# MCU.net
KiCad netlist of a schematic drawn in Altium Designer
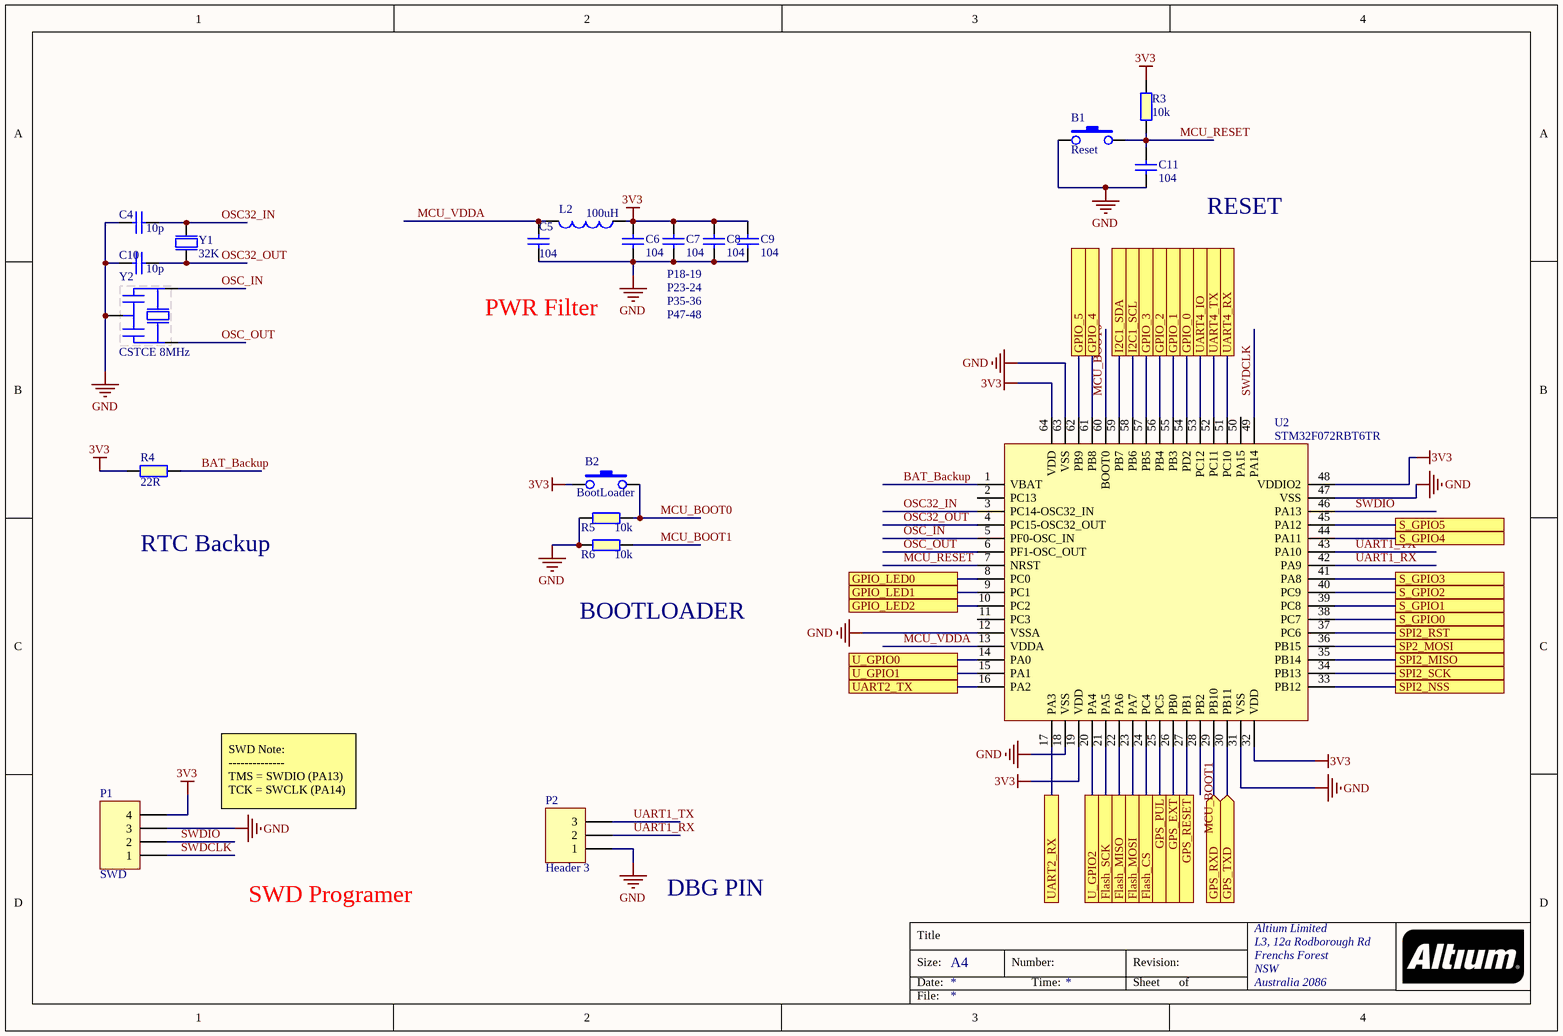
[diagram p0: MCU.SchDoc]

(export (version "E")
  (design (tool "Eeschema 10.0.6"))
  (components
    (comp (ref "B1")
      (value "Reset")
      (footprint "ThanhNT:TACTILE-SWITCH-1101NE")
      (libsource (lib "ThanhNT") (part "Button_2P_SMD"))
    )
    (comp (ref "B2")
      (value "BootLoader")
      (footprint "ThanhNT:TACTILE-SWITCH-1101NE")
      (libsource (lib "ThanhNT") (part "Button_2P_SMD"))
    )
    (comp (ref "C4")
      (value "10p")
      (footprint "C_0603")
      (description "Capacitor SMD")
      (fields (field (name "PUBLISHER") "Altium Limited"))
      (libsource (lib "ThanhNT") (part "Cap SMD 0805"))
    )
    (comp (ref "C5")
      (value "104")
      (footprint "C_0603")
      (description "Capacitor SMD")
      (fields (field (name "PUBLISHER") "Altium Limited"))
      (libsource (lib "ThanhNT") (part "Cap SMD 0805"))
    )
    (comp (ref "C6")
      (value "104")
      (footprint "C_0603")
      (description "Capacitor SMD")
      (fields (field (name "PUBLISHER") "Altium Limited"))
      (libsource (lib "ThanhNT") (part "Cap SMD 0805"))
    )
    (comp (ref "C7")
      (value "104")
      (footprint "C_0603")
      (description "Capacitor SMD")
      (fields (field (name "PUBLISHER") "Altium Limited"))
      (libsource (lib "ThanhNT") (part "Cap SMD 0805"))
    )
    (comp (ref "C8")
      (value "104")
      (footprint "C_0603")
      (description "Capacitor SMD")
      (fields (field (name "PUBLISHER") "Altium Limited"))
      (libsource (lib "ThanhNT") (part "Cap SMD 0805"))
    )
    (comp (ref "C9")
      (value "104")
      (footprint "C_0603")
      (description "Capacitor SMD")
      (fields (field (name "PUBLISHER") "Altium Limited"))
      (libsource (lib "ThanhNT") (part "Cap SMD 0805"))
    )
    (comp (ref "C10")
      (value "10p")
      (footprint "C_0603")
      (description "Capacitor SMD")
      (fields (field (name "PUBLISHER") "Altium Limited"))
      (libsource (lib "ThanhNT") (part "Cap SMD 0805"))
    )
    (comp (ref "C11")
      (value "104")
      (footprint "C_0603")
      (description "Capacitor SMD")
      (fields (field (name "PUBLISHER") "Altium Limited"))
      (libsource (lib "ThanhNT") (part "Cap SMD 0805"))
    )
    (comp (ref "L2")
      (value "100uH")
      (footprint "INDUCTOR_0603")
      (libsource (lib "ThanhNT") (part "INDUCTOR_0805"))
    )
    (comp (ref "P1")
      (value "SWD")
      (footprint "HDR1X4")
      (description "Header, 4-Pin")
      (fields (field (name "PUBLISHER") "Altium Limited"))
      (libsource (lib "Header") (part "Header 4"))
    )
    (comp (ref "P2")
      (value "Header 3")
      (footprint "HDR1X3")
      (description "Header, 3-Pin")
      (fields (field (name "PUBLISHER") "Altium Limited"))
      (libsource (lib "Header") (part "Header 3"))
    )
    (comp (ref "R3") (value "10k") (footprint "R_0603") (libsource (lib "ThanhNT") (part "RESISTOR_0805")))
    (comp (ref "R4") (value "22R") (footprint "R_0603") (libsource (lib "") (part "RESISTOR_0805_1")))
    (comp (ref "R5") (value "10k") (footprint "R_0603") (libsource (lib "") (part "RESISTOR_0805_1")))
    (comp (ref "R6") (value "10k") (footprint "R_0603") (libsource (lib "") (part "RESISTOR_0805_1")))
    (comp (ref "U2")
      (value "STM32F072RBT6TR")
      (footprint "STM32L072RBT")
      (description "IC MCU 32BIT 128KB FLASH 64LQFP")
      (fields
        (field (name "MANUFACTURER") "STMicroelectronics")
        (field (name "MANUFACTURER PART NUMBER") "STM32F072RBT6")
      )
      (libsource (lib "Node") (part "STM32F072RBT6TR"))
    )
    (comp (ref "Y1")
      (value "32K")
      (footprint "Crystal_2P")
      (fields (field (name "Comment") "Crystal_2P"))
      (libsource (lib "ThanhNT") (part "Crystal_2P"))
    )
    (comp (ref "Y2")
      (value "CSTCE 8MHz")
      (footprint "Crystal_4P")
      (description "(T) Crystal MHz with Capacitance Built-in")
      (libsource (lib "ThanhNT") (part "Crystal_CSTCE"))
    )
  )
  (nets
    (net (code "1") (name "/BAT_Backup") (class "Default")
      (node (ref "R4") (pin "2") (pinfunction "2_2") (pintype "passive"))
      (node (ref "U2") (pin "1") (pinfunction "VBAT_1") (pintype "passive"))
    )
    (net (code "2") (name "/Flash_CS") (class "Default")
      (node (ref "U2") (pin "24") (pinfunction "PC4_24") (pintype "passive"))
    )
    (net (code "3") (name "/Flash_MISO") (class "Default")
      (node (ref "U2") (pin "22") (pinfunction "PA6_22") (pintype "passive"))
    )
    (net (code "4") (name "/Flash_MOSI") (class "Default")
      (node (ref "U2") (pin "23") (pinfunction "PA7_23") (pintype "passive"))
    )
    (net (code "5") (name "/Flash_SCK") (class "Default")
      (node (ref "U2") (pin "21") (pinfunction "PA5_21") (pintype "passive"))
    )
    (net (code "6") (name "/GPIO_0") (class "Default")
      (node (ref "U2") (pin "54") (pinfunction "PD2_54") (pintype "passive"))
    )
    (net (code "7") (name "/GPIO_1") (class "Default")
      (node (ref "U2") (pin "55") (pinfunction "PB3_55") (pintype "passive"))
    )
    (net (code "8") (name "/GPIO_2") (class "Default")
      (node (ref "U2") (pin "56") (pinfunction "PB4_56") (pintype "passive"))
    )
    (net (code "9") (name "/GPIO_3") (class "Default")
      (node (ref "U2") (pin "57") (pinfunction "PB5_57") (pintype "passive"))
    )
    (net (code "10") (name "/GPIO_4") (class "Default")
      (node (ref "U2") (pin "61") (pinfunction "PB8_61") (pintype "passive"))
    )
    (net (code "11") (name "/GPIO_5") (class "Default")
      (node (ref "U2") (pin "62") (pinfunction "PB9_62") (pintype "passive"))
    )
    (net (code "12") (name "/GPIO_LED0") (class "Default")
      (node (ref "U2") (pin "8") (pinfunction "PC0_8") (pintype "passive"))
    )
    (net (code "13") (name "/GPIO_LED1") (class "Default")
      (node (ref "U2") (pin "9") (pinfunction "PC1_9") (pintype "passive"))
    )
    (net (code "14") (name "/GPIO_LED2") (class "Default")
      (node (ref "U2") (pin "10") (pinfunction "PC2_10") (pintype "passive"))
    )
    (net (code "15") (name "/GPS_EXT") (class "Default")
      (node (ref "U2") (pin "26") (pinfunction "PB0_26") (pintype "passive"))
    )
    (net (code "16") (name "/GPS_PUL") (class "Default")
      (node (ref "U2") (pin "25") (pinfunction "PC5_25") (pintype "passive"))
    )
    (net (code "17") (name "/GPS_RESET") (class "Default")
      (node (ref "U2") (pin "27") (pinfunction "PB1_27") (pintype "passive"))
    )
    (net (code "18") (name "/GPS_RXD") (class "Default")
      (node (ref "U2") (pin "29") (pinfunction "PB10_29") (pintype "passive"))
    )
    (net (code "19") (name "/GPS_TXD") (class "Default")
      (node (ref "U2") (pin "30") (pinfunction "PB11_30") (pintype "passive"))
    )
    (net (code "20") (name "/I2C1_SCL") (class "Default")
      (node (ref "U2") (pin "58") (pinfunction "PB6_58") (pintype "passive"))
    )
    (net (code "21") (name "/I2C1_SDA") (class "Default")
      (node (ref "U2") (pin "59") (pinfunction "PB7_59") (pintype "passive"))
    )
    (net (code "22") (name "/MCU_BOOT0") (class "Default")
      (node (ref "B2") (pin "2") (pinfunction "2_2") (pintype "passive"))
      (node (ref "R5") (pin "2") (pinfunction "2_2") (pintype "passive"))
      (node (ref "U2") (pin "60") (pinfunction "BOOT0_60") (pintype "passive"))
    )
    (net (code "23") (name "/MCU_BOOT1") (class "Default")
      (node (ref "R6") (pin "2") (pinfunction "2_2") (pintype "passive"))
      (node (ref "U2") (pin "28") (pinfunction "PB2_28") (pintype "passive"))
    )
    (net (code "24") (name "/MCU_RESET") (class "Default")
      (node (ref "B1") (pin "2") (pinfunction "2_2") (pintype "passive"))
      (node (ref "C11") (pin "1") (pinfunction "1_1") (pintype "passive"))
      (node (ref "R3") (pin "2") (pinfunction "2_2") (pintype "passive"))
      (node (ref "U2") (pin "7") (pinfunction "NRST_7") (pintype "passive"))
    )
    (net (code "25") (name "/MCU_VDDA") (class "Default")
      (node (ref "C5") (pin "2") (pinfunction "2_2") (pintype "passive"))
      (node (ref "L2") (pin "2") (pinfunction "2_2") (pintype "passive"))
      (node (ref "U2") (pin "13") (pinfunction "VDDA_13") (pintype "passive"))
    )
    (net (code "26") (name "/OSC32_IN") (class "Default")
      (node (ref "C4") (pin "2") (pinfunction "2_2") (pintype "passive"))
      (node (ref "U2") (pin "3") (pinfunction "PC14-OSC32_IN_3") (pintype "passive"))
      (node (ref "Y1") (pin "2") (pintype "passive"))
    )
    (net (code "27") (name "/OSC32_OUT") (class "Default")
      (node (ref "C10") (pin "2") (pinfunction "2_2") (pintype "passive"))
      (node (ref "U2") (pin "4") (pinfunction "PC15-OSC32_OUT_4") (pintype "passive"))
      (node (ref "Y1") (pin "1") (pintype "passive"))
    )
    (net (code "28") (name "/OSC_IN") (class "Default")
      (node (ref "U2") (pin "5") (pinfunction "PF0-OSC_IN_5") (pintype "passive"))
      (node (ref "Y2") (pin "1") (pinfunction "1_1") (pintype "passive"))
    )
    (net (code "29") (name "/OSC_OUT") (class "Default")
      (node (ref "U2") (pin "6") (pinfunction "PF1-OSC_OUT_6") (pintype "passive"))
      (node (ref "Y2") (pin "3") (pinfunction "3_3") (pintype "passive"))
    )
    (net (code "30") (name "/SP2_MOSI") (class "Default")
      (node (ref "U2") (pin "36") (pinfunction "PB15_36") (pintype "passive"))
    )
    (net (code "31") (name "/SPI2_MISO") (class "Default")
      (node (ref "U2") (pin "35") (pinfunction "PB14_35") (pintype "passive"))
    )
    (net (code "32") (name "/SPI2_NSS") (class "Default")
      (node (ref "U2") (pin "33") (pinfunction "PB12_33") (pintype "passive"))
    )
    (net (code "33") (name "/SPI2_RST") (class "Default")
      (node (ref "U2") (pin "37") (pinfunction "PC6_37") (pintype "passive"))
    )
    (net (code "34") (name "/SPI2_SCK") (class "Default")
      (node (ref "U2") (pin "34") (pinfunction "PB13_34") (pintype "passive"))
    )
    (net (code "35") (name "/SWDCLK") (class "Default")
      (node (ref "P1") (pin "1") (pinfunction "1_1") (pintype "passive"))
      (node (ref "U2") (pin "49") (pinfunction "PA14_49") (pintype "passive"))
    )
    (net (code "36") (name "/SWDIO") (class "Default")
      (node (ref "P1") (pin "2") (pinfunction "2_2") (pintype "passive"))
      (node (ref "U2") (pin "46") (pinfunction "PA13_46") (pintype "passive"))
    )
    (net (code "37") (name "/S_GPIO0") (class "Default")
      (node (ref "U2") (pin "38") (pinfunction "PC7_38") (pintype "passive"))
    )
    (net (code "38") (name "/S_GPIO1") (class "Default")
      (node (ref "U2") (pin "39") (pinfunction "PC8_39") (pintype "passive"))
    )
    (net (code "39") (name "/S_GPIO2") (class "Default")
      (node (ref "U2") (pin "40") (pinfunction "PC9_40") (pintype "passive"))
    )
    (net (code "40") (name "/S_GPIO3") (class "Default")
      (node (ref "U2") (pin "41") (pinfunction "PA8_41") (pintype "passive"))
    )
    (net (code "41") (name "/S_GPIO4") (class "Default")
      (node (ref "U2") (pin "44") (pinfunction "PA11_44") (pintype "passive"))
    )
    (net (code "42") (name "/S_GPIO5") (class "Default")
      (node (ref "U2") (pin "45") (pinfunction "PA12_45") (pintype "passive"))
    )
    (net (code "43") (name "/UART1_RX") (class "Default")
      (node (ref "P2") (pin "2") (pinfunction "2_2") (pintype "passive"))
      (node (ref "U2") (pin "42") (pinfunction "PA9_42") (pintype "passive"))
    )
    (net (code "44") (name "/UART1_TX") (class "Default")
      (node (ref "P2") (pin "3") (pinfunction "3_3") (pintype "passive"))
      (node (ref "U2") (pin "43") (pinfunction "PA10_43") (pintype "passive"))
    )
    (net (code "45") (name "/UART2_RX") (class "Default")
      (node (ref "U2") (pin "17") (pinfunction "PA3_17") (pintype "passive"))
    )
    (net (code "46") (name "/UART2_TX") (class "Default")
      (node (ref "U2") (pin "16") (pinfunction "PA2_16") (pintype "passive"))
    )
    (net (code "47") (name "/UART4_IO") (class "Default")
      (node (ref "U2") (pin "53") (pinfunction "PC12_53") (pintype "passive"))
    )
    (net (code "48") (name "/UART4_RX") (class "Default")
      (node (ref "U2") (pin "51") (pinfunction "PC10_51") (pintype "passive"))
    )
    (net (code "49") (name "/UART4_TX") (class "Default")
      (node (ref "U2") (pin "52") (pinfunction "PC11_52") (pintype "passive"))
    )
    (net (code "50") (name "/U_GPIO0") (class "Default")
      (node (ref "U2") (pin "14") (pinfunction "PA0_14") (pintype "passive"))
    )
    (net (code "51") (name "/U_GPIO1") (class "Default")
      (node (ref "U2") (pin "15") (pinfunction "PA1_15") (pintype "passive"))
    )
    (net (code "52") (name "/U_GPIO2") (class "Default")
      (node (ref "U2") (pin "20") (pinfunction "PA4_20") (pintype "passive"))
    )
    (net (code "53") (name "3V3") (class "Default")
      (node (ref "B2") (pin "1") (pinfunction "1_1") (pintype "passive"))
      (node (ref "C6") (pin "2") (pinfunction "2_2") (pintype "passive"))
      (node (ref "C7") (pin "2") (pinfunction "2_2") (pintype "passive"))
      (node (ref "C8") (pin "2") (pinfunction "2_2") (pintype "passive"))
      (node (ref "C9") (pin "2") (pinfunction "2_2") (pintype "passive"))
      (node (ref "L2") (pin "1") (pinfunction "1_1") (pintype "passive"))
      (node (ref "P1") (pin "4") (pinfunction "4_4") (pintype "passive"))
      (node (ref "R3") (pin "1") (pinfunction "1_1") (pintype "passive"))
      (node (ref "R4") (pin "1") (pinfunction "1_1") (pintype "passive"))
      (node (ref "U2") (pin "19") (pinfunction "VDD_19") (pintype "passive"))
      (node (ref "U2") (pin "32") (pinfunction "VDD_32") (pintype "passive"))
      (node (ref "U2") (pin "48") (pinfunction "VDDIO2_48") (pintype "passive"))
      (node (ref "U2") (pin "64") (pinfunction "VDD_64") (pintype "passive"))
    )
    (net (code "54") (name "GND") (class "Default")
      (node (ref "B1") (pin "1") (pinfunction "1_1") (pintype "passive"))
      (node (ref "C10") (pin "1") (pinfunction "1_1") (pintype "passive"))
      (node (ref "C11") (pin "2") (pinfunction "2_2") (pintype "passive"))
      (node (ref "C4") (pin "1") (pinfunction "1_1") (pintype "passive"))
      (node (ref "C5") (pin "1") (pinfunction "1_1") (pintype "passive"))
      (node (ref "C6") (pin "1") (pinfunction "1_1") (pintype "passive"))
      (node (ref "C7") (pin "1") (pinfunction "1_1") (pintype "passive"))
      (node (ref "C8") (pin "1") (pinfunction "1_1") (pintype "passive"))
      (node (ref "C9") (pin "1") (pinfunction "1_1") (pintype "passive"))
      (node (ref "P1") (pin "3") (pinfunction "3_3") (pintype "passive"))
      (node (ref "P2") (pin "1") (pinfunction "1_1") (pintype "passive"))
      (node (ref "R5") (pin "1") (pinfunction "1_1") (pintype "passive"))
      (node (ref "R6") (pin "1") (pinfunction "1_1") (pintype "passive"))
      (node (ref "U2") (pin "12") (pinfunction "VSSA_12") (pintype "passive"))
      (node (ref "U2") (pin "18") (pinfunction "VSS_18") (pintype "passive"))
      (node (ref "U2") (pin "31") (pinfunction "VSS_31") (pintype "passive"))
      (node (ref "U2") (pin "47") (pinfunction "VSS_47") (pintype "passive"))
      (node (ref "U2") (pin "63") (pinfunction "VSS_63") (pintype "passive"))
      (node (ref "Y2") (pin "2") (pinfunction "2_2") (pintype "passive"))
    )
    (net (code "55") (name "unconnected-(U2-PA15-Pad50)") (class "Default")
      (node (ref "U2") (pin "50") (pinfunction "PA15_50") (pintype "passive"))
    )
    (net (code "56") (name "unconnected-(U2-PC3-Pad11)") (class "Default")
      (node (ref "U2") (pin "11") (pinfunction "PC3_11") (pintype "passive"))
    )
    (net (code "57") (name "unconnected-(U2-PC13-Pad2)") (class "Default")
      (node (ref "U2") (pin "2") (pinfunction "PC13_2") (pintype "passive"))
    )
  )
)
